# FM-Radio-Simple-Receiver.net
KiCad netlist of a schematic drawn in EAGLE
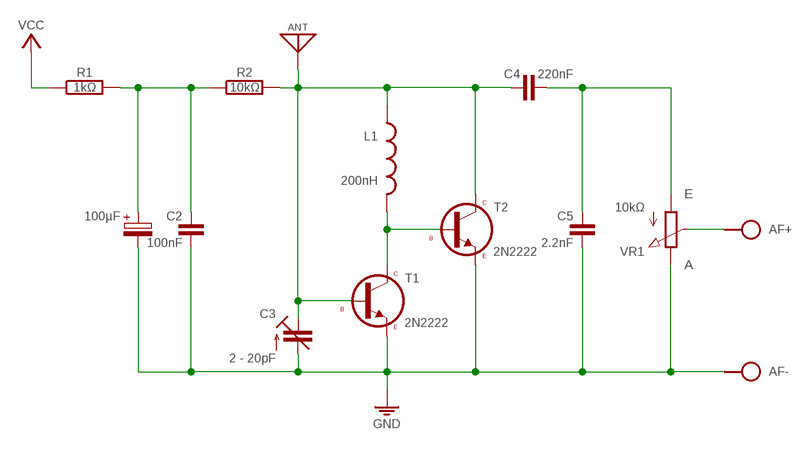
[diagram p0: schematic, sheet 1]

(export (version "E")
  (design (tool "Eeschema 10.0.6"))
  (components
    (comp (ref "100µF")
      (value "CPOLE2,5-5/V")
      (footprint "eagle-import:E2,5-5_V")
      (libsource (lib "eagle-import") (part "CPOLE2,5-5/V"))
    )
    (comp (ref "AF")
      (value "SPAD+-+-")
      (footprint "eagle-import:SPAD+-")
      (libsource (lib "eagle-import") (part "SPAD+-+-"))
    )
    (comp (ref "ANT")
      (value "ANT")
      (footprint "eagle-import:SPAD")
      (libsource (lib "eagle-import") (part "ANT"))
    )
    (comp (ref "BAT")
      (value "VCC_GNDL")
      (footprint "eagle-import:SPAD-+")
      (libsource (lib "eagle-import") (part "VCC_GNDL"))
    )
    (comp (ref "C2")
      (value "100nF")
      (footprint "eagle-import:C050-020X036_V")
      (libsource (lib "eagle-import") (part "C050-020X036/V"))
    )
    (comp (ref "C3")
      (value "2 - 20pF")
      (footprint "eagle-import:TRIM-2222-808")
      (libsource (lib "eagle-import") (part "C-TR-PH20127"))
    )
    (comp (ref "C4")
      (value "220nF")
      (footprint "eagle-import:C050-020X044")
      (libsource (lib "eagle-import") (part "C-H050-020X044"))
    )
    (comp (ref "C5")
      (value "2.2nF")
      (footprint "eagle-import:C050-020X036_V")
      (libsource (lib "eagle-import") (part "C050-020X036/V"))
    )
    (comp (ref "L1")
      (value "200nH")
      (footprint "eagle-import:L-04_7-V")
      (libsource (lib "eagle-import") (part "L04/7-V"))
    )
    (comp (ref "R1")
      (value "1kΩ")
      (footprint "eagle-import:0204_10")
      (libsource (lib "eagle-import") (part "R-H0204/10"))
    )
    (comp (ref "R2")
      (value "10kΩ")
      (footprint "eagle-import:0204_10")
      (libsource (lib "eagle-import") (part "R-H0204/10"))
    )
    (comp (ref "T1")
      (value "2N2222")
      (footprint "eagle-import:TO92-EBC")
      (libsource (lib "eagle-import") (part "2N2222"))
    )
    (comp (ref "T2")
      (value "2N2222")
      (footprint "eagle-import:TO92-EBC")
      (libsource (lib "eagle-import") (part "2N2222"))
    )
    (comp (ref "VR1")
      (value "10kΩ")
      (footprint "eagle-import:POT")
      (libsource (lib "eagle-import") (part "POT"))
    )
  )
  (nets
    (net (code "1") (name "Net-(100µF-Pad+)") (class "Default")
      (node (ref "100µF") (pin "+") (pinfunction "+_+") (pintype "passive"))
      (node (ref "C2") (pin "1") (pinfunction "1_1") (pintype "passive"))
      (node (ref "R1") (pin "2") (pinfunction "2_2") (pintype "passive"))
      (node (ref "R2") (pin "1") (pinfunction "1_1") (pintype "passive"))
    )
    (net (code "2") (name "Net-(AFA-P$1)") (class "Default")
      (node (ref "AF") (pin "2") (pinfunction "P$1_2") (pintype "passive"))
      (node (ref "VR1") (pin "S") (pinfunction "S_S") (pintype "passive"))
    )
    (net (code "3") (name "Net-(AFB-P$1)") (class "Default")
      (node (ref "100µF") (pin "-") (pinfunction "-_-") (pintype "passive"))
      (node (ref "AF") (pin "1") (pinfunction "P$1_1") (pintype "passive"))
      (node (ref "BAT") (pin "1") (pinfunction "GND_1") (pintype "power_in"))
      (node (ref "C2") (pin "2") (pinfunction "2_2") (pintype "passive"))
      (node (ref "C3") (pin "1") (pinfunction "A_1") (pintype "passive"))
      (node (ref "C3") (pin "3") (pinfunction "A_3") (pintype "passive"))
      (node (ref "C5") (pin "2") (pinfunction "2_2") (pintype "passive"))
      (node (ref "T1") (pin "E") (pinfunction "E_E") (pintype "passive"))
      (node (ref "T2") (pin "E") (pinfunction "E_E") (pintype "passive"))
      (node (ref "VR1") (pin "E") (pinfunction "E_E") (pintype "passive"))
    )
    (net (code "4") (name "Net-(BATA-VCC)") (class "Default")
      (node (ref "BAT") (pin "2") (pinfunction "VCC_2") (pintype "power_in"))
      (node (ref "R1") (pin "1") (pinfunction "1_1") (pintype "passive"))
    )
    (net (code "5") (name "Net-(C3-E)") (class "Default")
      (node (ref "ANT") (pin "1") (pinfunction "1_1") (pintype "output"))
      (node (ref "C3") (pin "2") (pinfunction "E_2") (pintype "passive"))
      (node (ref "C4") (pin "1") (pinfunction "1_1") (pintype "passive"))
      (node (ref "L1") (pin "1") (pinfunction "1_1") (pintype "passive"))
      (node (ref "R2") (pin "2") (pinfunction "2_2") (pintype "passive"))
      (node (ref "T1") (pin "B") (pinfunction "B_B") (pintype "passive"))
      (node (ref "T2") (pin "C") (pinfunction "C_C") (pintype "passive"))
    )
    (net (code "6") (name "Net-(C4-Pad2)") (class "Default")
      (node (ref "C4") (pin "2") (pinfunction "2_2") (pintype "passive"))
      (node (ref "C5") (pin "1") (pinfunction "1_1") (pintype "passive"))
      (node (ref "VR1") (pin "A") (pinfunction "A_A") (pintype "passive"))
    )
    (net (code "7") (name "Net-(L1-Pad2)") (class "Default")
      (node (ref "L1") (pin "2") (pinfunction "2_2") (pintype "passive"))
      (node (ref "T1") (pin "C") (pinfunction "C_C") (pintype "passive"))
      (node (ref "T2") (pin "B") (pinfunction "B_B") (pintype "passive"))
    )
  )
)
